# esp32_m5_shield.net
KiCad netlist of a schematic drawn in EAGLE
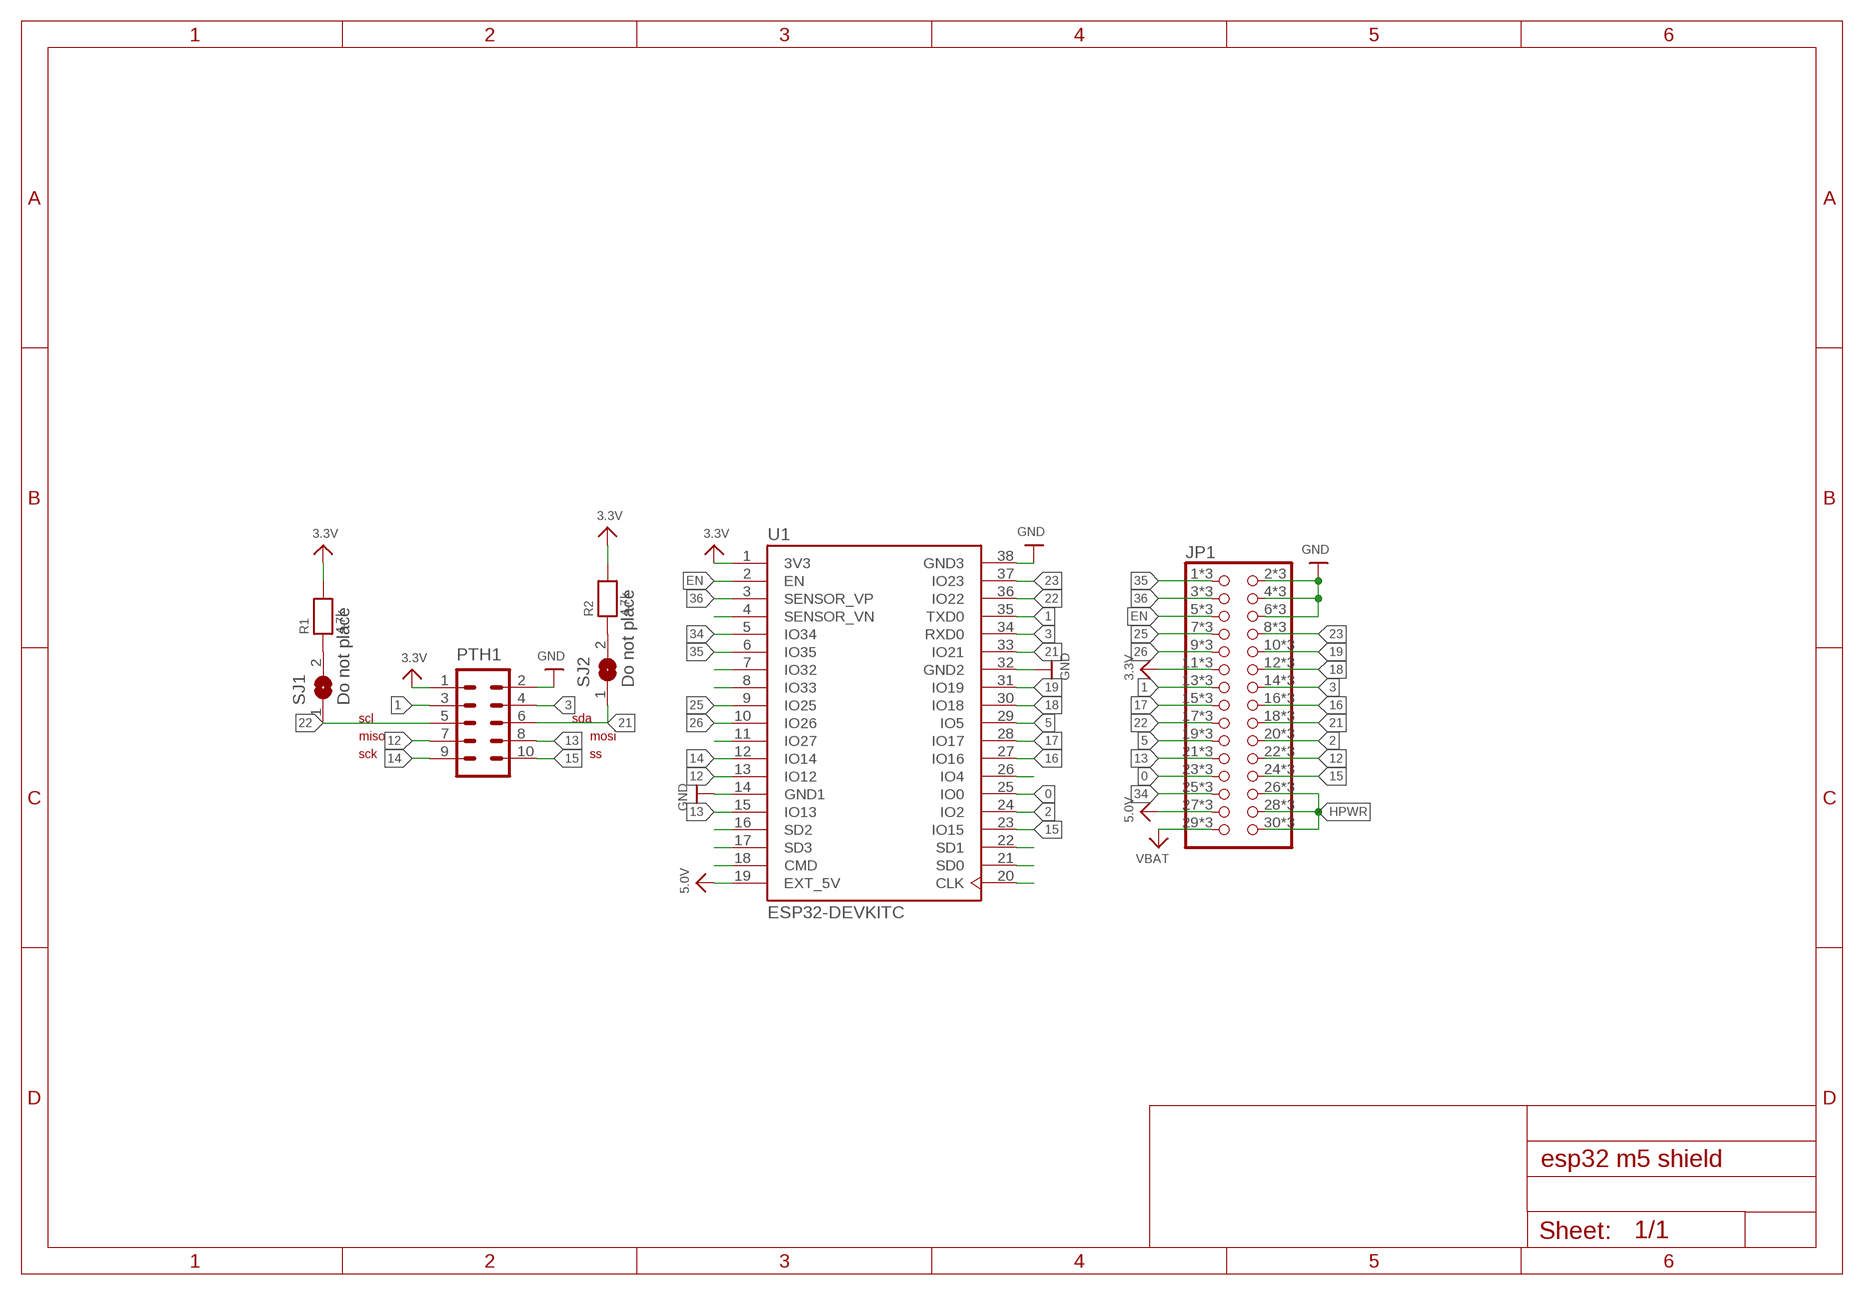
[diagram p0: schematic, sheet 1]

(export (version "E")
  (design (tool "Eeschema 10.0.6"))
  (components
    (comp (ref "JP1")
      (value "PINHD-2X15")
      (footprint "eagle-import:2X15")
      (libsource (lib "eagle-import") (part "PINHD-2X15"))
    )
    (comp (ref "PTH1")
      (value "ML10PTH")
      (footprint "eagle-import:ML10-MALE")
      (libsource (lib "eagle-import") (part "ML10PTH"))
    )
    (comp (ref "R1")
      (value "4.7k")
      (footprint "eagle-import:0603-MINI")
      (libsource (lib "eagle-import") (part "RESISTOR0603MINI"))
    )
    (comp (ref "R2")
      (value "4.7k")
      (footprint "eagle-import:0603-MINI")
      (libsource (lib "eagle-import") (part "RESISTOR0603MINI"))
    )
    (comp (ref "SJ1")
      (value "Do not place")
      (footprint "eagle-import:SOLDERJUMPER_CLOSEDWIRE")
      (libsource (lib "eagle-import") (part "SOLDERJUMPERCLOSED"))
    )
    (comp (ref "SJ2")
      (value "Do not place")
      (footprint "eagle-import:SOLDERJUMPER_CLOSEDWIRE")
      (libsource (lib "eagle-import") (part "SOLDERJUMPERCLOSED"))
    )
    (comp (ref "U1")
      (value "ESP32-DEVKITC")
      (footprint "eagle-import:MODULE_ESP32-DEVKITC")
      (fields (field (name "MF") "Espressif Systems"))
      (libsource (lib "eagle-import") (part "ESP32-DEVKITC"))
    )
  )
  (nets
    (net (code "1") (name "0") (class "Default")
      (node (ref "JP1") (pin "23") (pinfunction "23_23") (pintype "passive"))
      (node (ref "JP1") (pin "P$23") (pinfunction "23_P$23") (pintype "passive"))
      (node (ref "JP1") (pin "P$53") (pinfunction "23_P$53") (pintype "passive"))
      (node (ref "U1") (pin "25") (pinfunction "IO0_25") (pintype "bidirectional"))
    )
    (net (code "2") (name "1") (class "Default")
      (node (ref "JP1") (pin "13") (pinfunction "13_13") (pintype "passive"))
      (node (ref "JP1") (pin "P$13") (pinfunction "13_P$13") (pintype "passive"))
      (node (ref "JP1") (pin "P$43") (pinfunction "13_P$43") (pintype "passive"))
      (node (ref "PTH1") (pin "3") (pinfunction "3_3") (pintype "passive"))
      (node (ref "U1") (pin "35") (pinfunction "TXD0_35") (pintype "output"))
    )
    (net (code "3") (name "2") (class "Default")
      (node (ref "JP1") (pin "20") (pinfunction "20_20") (pintype "passive"))
      (node (ref "JP1") (pin "P$20") (pinfunction "20_P$20") (pintype "passive"))
      (node (ref "JP1") (pin "P$50") (pinfunction "20_P$50") (pintype "passive"))
      (node (ref "U1") (pin "24") (pinfunction "IO2_24") (pintype "bidirectional"))
    )
    (net (code "4") (name "3") (class "Default")
      (node (ref "JP1") (pin "14") (pinfunction "14_14") (pintype "passive"))
      (node (ref "JP1") (pin "P$14") (pinfunction "14_P$14") (pintype "passive"))
      (node (ref "JP1") (pin "P$44") (pinfunction "14_P$44") (pintype "passive"))
      (node (ref "PTH1") (pin "4") (pinfunction "4_4") (pintype "passive"))
      (node (ref "U1") (pin "34") (pinfunction "RXD0_34") (pintype "input"))
    )
    (net (code "5") (name "3.3V") (class "Default")
      (node (ref "JP1") (pin "11") (pinfunction "11_11") (pintype "passive"))
      (node (ref "JP1") (pin "P$11") (pinfunction "11_P$11") (pintype "passive"))
      (node (ref "JP1") (pin "P$41") (pinfunction "11_P$41") (pintype "passive"))
      (node (ref "PTH1") (pin "1") (pinfunction "1_1") (pintype "passive"))
      (node (ref "R1") (pin "2") (pinfunction "2_2") (pintype "passive"))
      (node (ref "R2") (pin "2") (pinfunction "2_2") (pintype "passive"))
      (node (ref "U1") (pin "1") (pinfunction "3V3_1") (pintype "power_in"))
    )
    (net (code "6") (name "5") (class "Default")
      (node (ref "JP1") (pin "19") (pinfunction "19_19") (pintype "passive"))
      (node (ref "JP1") (pin "P$19") (pinfunction "19_P$19") (pintype "passive"))
      (node (ref "JP1") (pin "P$49") (pinfunction "19_P$49") (pintype "passive"))
      (node (ref "U1") (pin "29") (pinfunction "IO5_29") (pintype "bidirectional"))
    )
    (net (code "7") (name "5.0V") (class "Default")
      (node (ref "JP1") (pin "27") (pinfunction "27_27") (pintype "passive"))
      (node (ref "JP1") (pin "P$27") (pinfunction "27_P$27") (pintype "passive"))
      (node (ref "JP1") (pin "P$57") (pinfunction "27_P$57") (pintype "passive"))
      (node (ref "U1") (pin "19") (pinfunction "EXT_5V_19") (pintype "power_in"))
    )
    (net (code "8") (name "12") (class "Default")
      (node (ref "JP1") (pin "22") (pinfunction "22_22") (pintype "passive"))
      (node (ref "JP1") (pin "P$22") (pinfunction "22_P$22") (pintype "passive"))
      (node (ref "JP1") (pin "P$52") (pinfunction "22_P$52") (pintype "passive"))
      (node (ref "PTH1") (pin "7") (pinfunction "7_7") (pintype "passive"))
      (node (ref "U1") (pin "13") (pinfunction "IO12_13") (pintype "bidirectional"))
    )
    (net (code "9") (name "13") (class "Default")
      (node (ref "JP1") (pin "21") (pinfunction "21_21") (pintype "passive"))
      (node (ref "JP1") (pin "P$21") (pinfunction "21_P$21") (pintype "passive"))
      (node (ref "JP1") (pin "P$51") (pinfunction "21_P$51") (pintype "passive"))
      (node (ref "PTH1") (pin "8") (pinfunction "8_8") (pintype "passive"))
      (node (ref "U1") (pin "15") (pinfunction "IO13_15") (pintype "bidirectional"))
    )
    (net (code "10") (name "14") (class "Default")
      (node (ref "PTH1") (pin "9") (pinfunction "9_9") (pintype "passive"))
      (node (ref "U1") (pin "12") (pinfunction "IO14_12") (pintype "bidirectional"))
    )
    (net (code "11") (name "15") (class "Default")
      (node (ref "JP1") (pin "24") (pinfunction "24_24") (pintype "passive"))
      (node (ref "JP1") (pin "P$24") (pinfunction "24_P$24") (pintype "passive"))
      (node (ref "JP1") (pin "P$54") (pinfunction "24_P$54") (pintype "passive"))
      (node (ref "PTH1") (pin "10") (pinfunction "10_10") (pintype "passive"))
      (node (ref "U1") (pin "23") (pinfunction "IO15_23") (pintype "bidirectional"))
    )
    (net (code "12") (name "16") (class "Default")
      (node (ref "JP1") (pin "16") (pinfunction "16_16") (pintype "passive"))
      (node (ref "JP1") (pin "P$16") (pinfunction "16_P$16") (pintype "passive"))
      (node (ref "JP1") (pin "P$46") (pinfunction "16_P$46") (pintype "passive"))
      (node (ref "U1") (pin "27") (pinfunction "IO16_27") (pintype "bidirectional"))
    )
    (net (code "13") (name "17") (class "Default")
      (node (ref "JP1") (pin "15") (pinfunction "15_15") (pintype "passive"))
      (node (ref "JP1") (pin "P$15") (pinfunction "15_P$15") (pintype "passive"))
      (node (ref "JP1") (pin "P$45") (pinfunction "15_P$45") (pintype "passive"))
      (node (ref "U1") (pin "28") (pinfunction "IO17_28") (pintype "bidirectional"))
    )
    (net (code "14") (name "18") (class "Default")
      (node (ref "JP1") (pin "12") (pinfunction "12_12") (pintype "passive"))
      (node (ref "JP1") (pin "P$12") (pinfunction "12_P$12") (pintype "passive"))
      (node (ref "JP1") (pin "P$42") (pinfunction "12_P$42") (pintype "passive"))
      (node (ref "U1") (pin "30") (pinfunction "IO18_30") (pintype "bidirectional"))
    )
    (net (code "15") (name "19") (class "Default")
      (node (ref "JP1") (pin "10") (pinfunction "10_10") (pintype "passive"))
      (node (ref "JP1") (pin "P$10") (pinfunction "10_P$10") (pintype "passive"))
      (node (ref "JP1") (pin "P$40") (pinfunction "10_P$40") (pintype "passive"))
      (node (ref "U1") (pin "31") (pinfunction "IO19_31") (pintype "bidirectional"))
    )
    (net (code "16") (name "21") (class "Default")
      (node (ref "JP1") (pin "18") (pinfunction "18_18") (pintype "passive"))
      (node (ref "JP1") (pin "P$18") (pinfunction "18_P$18") (pintype "passive"))
      (node (ref "JP1") (pin "P$48") (pinfunction "18_P$48") (pintype "passive"))
      (node (ref "PTH1") (pin "6") (pinfunction "6_6") (pintype "passive"))
      (node (ref "SJ2") (pin "1") (pinfunction "1_1") (pintype "passive"))
      (node (ref "U1") (pin "33") (pinfunction "IO21_33") (pintype "bidirectional"))
    )
    (net (code "17") (name "22") (class "Default")
      (node (ref "JP1") (pin "17") (pinfunction "17_17") (pintype "passive"))
      (node (ref "JP1") (pin "P$17") (pinfunction "17_P$17") (pintype "passive"))
      (node (ref "JP1") (pin "P$47") (pinfunction "17_P$47") (pintype "passive"))
      (node (ref "PTH1") (pin "5") (pinfunction "5_5") (pintype "passive"))
      (node (ref "SJ1") (pin "1") (pinfunction "1_1") (pintype "passive"))
      (node (ref "U1") (pin "36") (pinfunction "IO22_36") (pintype "bidirectional"))
    )
    (net (code "18") (name "23") (class "Default")
      (node (ref "JP1") (pin "8") (pinfunction "8_8") (pintype "passive"))
      (node (ref "JP1") (pin "P$38") (pinfunction "8_P$38") (pintype "passive"))
      (node (ref "JP1") (pin "P$8") (pinfunction "8_P$8") (pintype "passive"))
      (node (ref "U1") (pin "37") (pinfunction "IO23_37") (pintype "bidirectional"))
    )
    (net (code "19") (name "25") (class "Default")
      (node (ref "JP1") (pin "7") (pinfunction "7_7") (pintype "passive"))
      (node (ref "JP1") (pin "P$37") (pinfunction "7_P$37") (pintype "passive"))
      (node (ref "JP1") (pin "P$7") (pinfunction "7_P$7") (pintype "passive"))
      (node (ref "U1") (pin "9") (pinfunction "IO25_9") (pintype "bidirectional"))
    )
    (net (code "20") (name "26") (class "Default")
      (node (ref "JP1") (pin "9") (pinfunction "9_9") (pintype "passive"))
      (node (ref "JP1") (pin "P$39") (pinfunction "9_P$39") (pintype "passive"))
      (node (ref "JP1") (pin "P$9") (pinfunction "9_P$9") (pintype "passive"))
      (node (ref "U1") (pin "10") (pinfunction "IO26_10") (pintype "bidirectional"))
    )
    (net (code "21") (name "34") (class "Default")
      (node (ref "JP1") (pin "25") (pinfunction "25_25") (pintype "passive"))
      (node (ref "JP1") (pin "P$25") (pinfunction "25_P$25") (pintype "passive"))
      (node (ref "JP1") (pin "P$55") (pinfunction "25_P$55") (pintype "passive"))
      (node (ref "U1") (pin "5") (pinfunction "IO34_5") (pintype "bidirectional"))
    )
    (net (code "22") (name "35") (class "Default")
      (node (ref "JP1") (pin "1") (pinfunction "1_1") (pintype "passive"))
      (node (ref "JP1") (pin "P$1") (pinfunction "1_P$1") (pintype "passive"))
      (node (ref "JP1") (pin "P$31") (pinfunction "1_P$31") (pintype "passive"))
      (node (ref "U1") (pin "6") (pinfunction "IO35_6") (pintype "bidirectional"))
    )
    (net (code "23") (name "36") (class "Default")
      (node (ref "JP1") (pin "3") (pinfunction "3_3") (pintype "passive"))
      (node (ref "JP1") (pin "P$3") (pinfunction "3_P$3") (pintype "passive"))
      (node (ref "JP1") (pin "P$33") (pinfunction "3_P$33") (pintype "passive"))
      (node (ref "U1") (pin "3") (pinfunction "SENSOR_VP_3") (pintype "input"))
    )
    (net (code "24") (name "EN") (class "Default")
      (node (ref "JP1") (pin "5") (pinfunction "5_5") (pintype "passive"))
      (node (ref "JP1") (pin "P$35") (pinfunction "5_P$35") (pintype "passive"))
      (node (ref "JP1") (pin "P$5") (pinfunction "5_P$5") (pintype "passive"))
      (node (ref "U1") (pin "2") (pinfunction "EN_2") (pintype "input"))
    )
    (net (code "25") (name "GND") (class "Default")
      (node (ref "JP1") (pin "2") (pinfunction "2_2") (pintype "passive"))
      (node (ref "JP1") (pin "4") (pinfunction "4_4") (pintype "passive"))
      (node (ref "JP1") (pin "6") (pinfunction "6_6") (pintype "passive"))
      (node (ref "JP1") (pin "P$2") (pinfunction "2_P$2") (pintype "passive"))
      (node (ref "JP1") (pin "P$32") (pinfunction "2_P$32") (pintype "passive"))
      (node (ref "JP1") (pin "P$34") (pinfunction "4_P$34") (pintype "passive"))
      (node (ref "JP1") (pin "P$36") (pinfunction "6_P$36") (pintype "passive"))
      (node (ref "JP1") (pin "P$4") (pinfunction "4_P$4") (pintype "passive"))
      (node (ref "JP1") (pin "P$6") (pinfunction "6_P$6") (pintype "passive"))
      (node (ref "PTH1") (pin "2") (pinfunction "2_2") (pintype "passive"))
      (node (ref "U1") (pin "14") (pinfunction "GND1_14") (pintype "power_in"))
      (node (ref "U1") (pin "32") (pinfunction "GND2_32") (pintype "power_in"))
      (node (ref "U1") (pin "38") (pinfunction "GND3_38") (pintype "power_in"))
    )
    (net (code "26") (name "HPWR") (class "Default")
      (node (ref "JP1") (pin "26") (pinfunction "26_26") (pintype "passive"))
      (node (ref "JP1") (pin "28") (pinfunction "28_28") (pintype "passive"))
      (node (ref "JP1") (pin "30") (pinfunction "30_30") (pintype "passive"))
      (node (ref "JP1") (pin "P$26") (pinfunction "26_P$26") (pintype "passive"))
      (node (ref "JP1") (pin "P$28") (pinfunction "28_P$28") (pintype "passive"))
      (node (ref "JP1") (pin "P$30") (pinfunction "30_P$30") (pintype "passive"))
      (node (ref "JP1") (pin "P$56") (pinfunction "26_P$56") (pintype "passive"))
      (node (ref "JP1") (pin "P$58") (pinfunction "28_P$58") (pintype "passive"))
      (node (ref "JP1") (pin "P$60") (pinfunction "30_P$60") (pintype "passive"))
    )
    (net (code "27") (name "Net-(R1-Pad1)") (class "Default")
      (node (ref "R1") (pin "1") (pinfunction "1_1") (pintype "passive"))
      (node (ref "SJ1") (pin "2") (pinfunction "2_2") (pintype "passive"))
    )
    (net (code "28") (name "Net-(R2-Pad1)") (class "Default")
      (node (ref "R2") (pin "1") (pinfunction "1_1") (pintype "passive"))
      (node (ref "SJ2") (pin "2") (pinfunction "2_2") (pintype "passive"))
    )
    (net (code "29") (name "VBAT") (class "Default")
      (node (ref "JP1") (pin "29") (pinfunction "29_29") (pintype "passive"))
      (node (ref "JP1") (pin "P$29") (pinfunction "29_P$29") (pintype "passive"))
      (node (ref "JP1") (pin "P$59") (pinfunction "29_P$59") (pintype "passive"))
    )
    (net (code "30") (name "unconnected-(U1-CLK-Pad20)") (class "Default")
      (node (ref "U1") (pin "20") (pinfunction "CLK_20") (pintype "input"))
    )
    (net (code "31") (name "unconnected-(U1-CMD-Pad18)") (class "Default")
      (node (ref "U1") (pin "18") (pinfunction "CMD_18") (pintype "bidirectional"))
    )
    (net (code "32") (name "unconnected-(U1-IO4-Pad26)") (class "Default")
      (node (ref "U1") (pin "26") (pinfunction "IO4_26") (pintype "bidirectional"))
    )
    (net (code "33") (name "unconnected-(U1-IO27-Pad11)") (class "Default")
      (node (ref "U1") (pin "11") (pinfunction "IO27_11") (pintype "bidirectional"))
    )
    (net (code "34") (name "unconnected-(U1-IO32-Pad7)") (class "Default")
      (node (ref "U1") (pin "7") (pinfunction "IO32_7") (pintype "bidirectional"))
    )
    (net (code "35") (name "unconnected-(U1-IO33-Pad8)") (class "Default")
      (node (ref "U1") (pin "8") (pinfunction "IO33_8") (pintype "bidirectional"))
    )
    (net (code "36") (name "unconnected-(U1-SD0-Pad21)") (class "Default")
      (node (ref "U1") (pin "21") (pinfunction "SD0_21") (pintype "bidirectional"))
    )
    (net (code "37") (name "unconnected-(U1-SD1-Pad22)") (class "Default")
      (node (ref "U1") (pin "22") (pinfunction "SD1_22") (pintype "bidirectional"))
    )
    (net (code "38") (name "unconnected-(U1-SD2-Pad16)") (class "Default")
      (node (ref "U1") (pin "16") (pinfunction "SD2_16") (pintype "bidirectional"))
    )
    (net (code "39") (name "unconnected-(U1-SD3-Pad17)") (class "Default")
      (node (ref "U1") (pin "17") (pinfunction "SD3_17") (pintype "bidirectional"))
    )
    (net (code "40") (name "unconnected-(U1-SENSOR_VN-Pad4)") (class "Default")
      (node (ref "U1") (pin "4") (pinfunction "SENSOR_VN_4") (pintype "input"))
    )
  )
)
